# voltage_sensor_v0_7.net
KiCad netlist of a schematic drawn in EAGLE
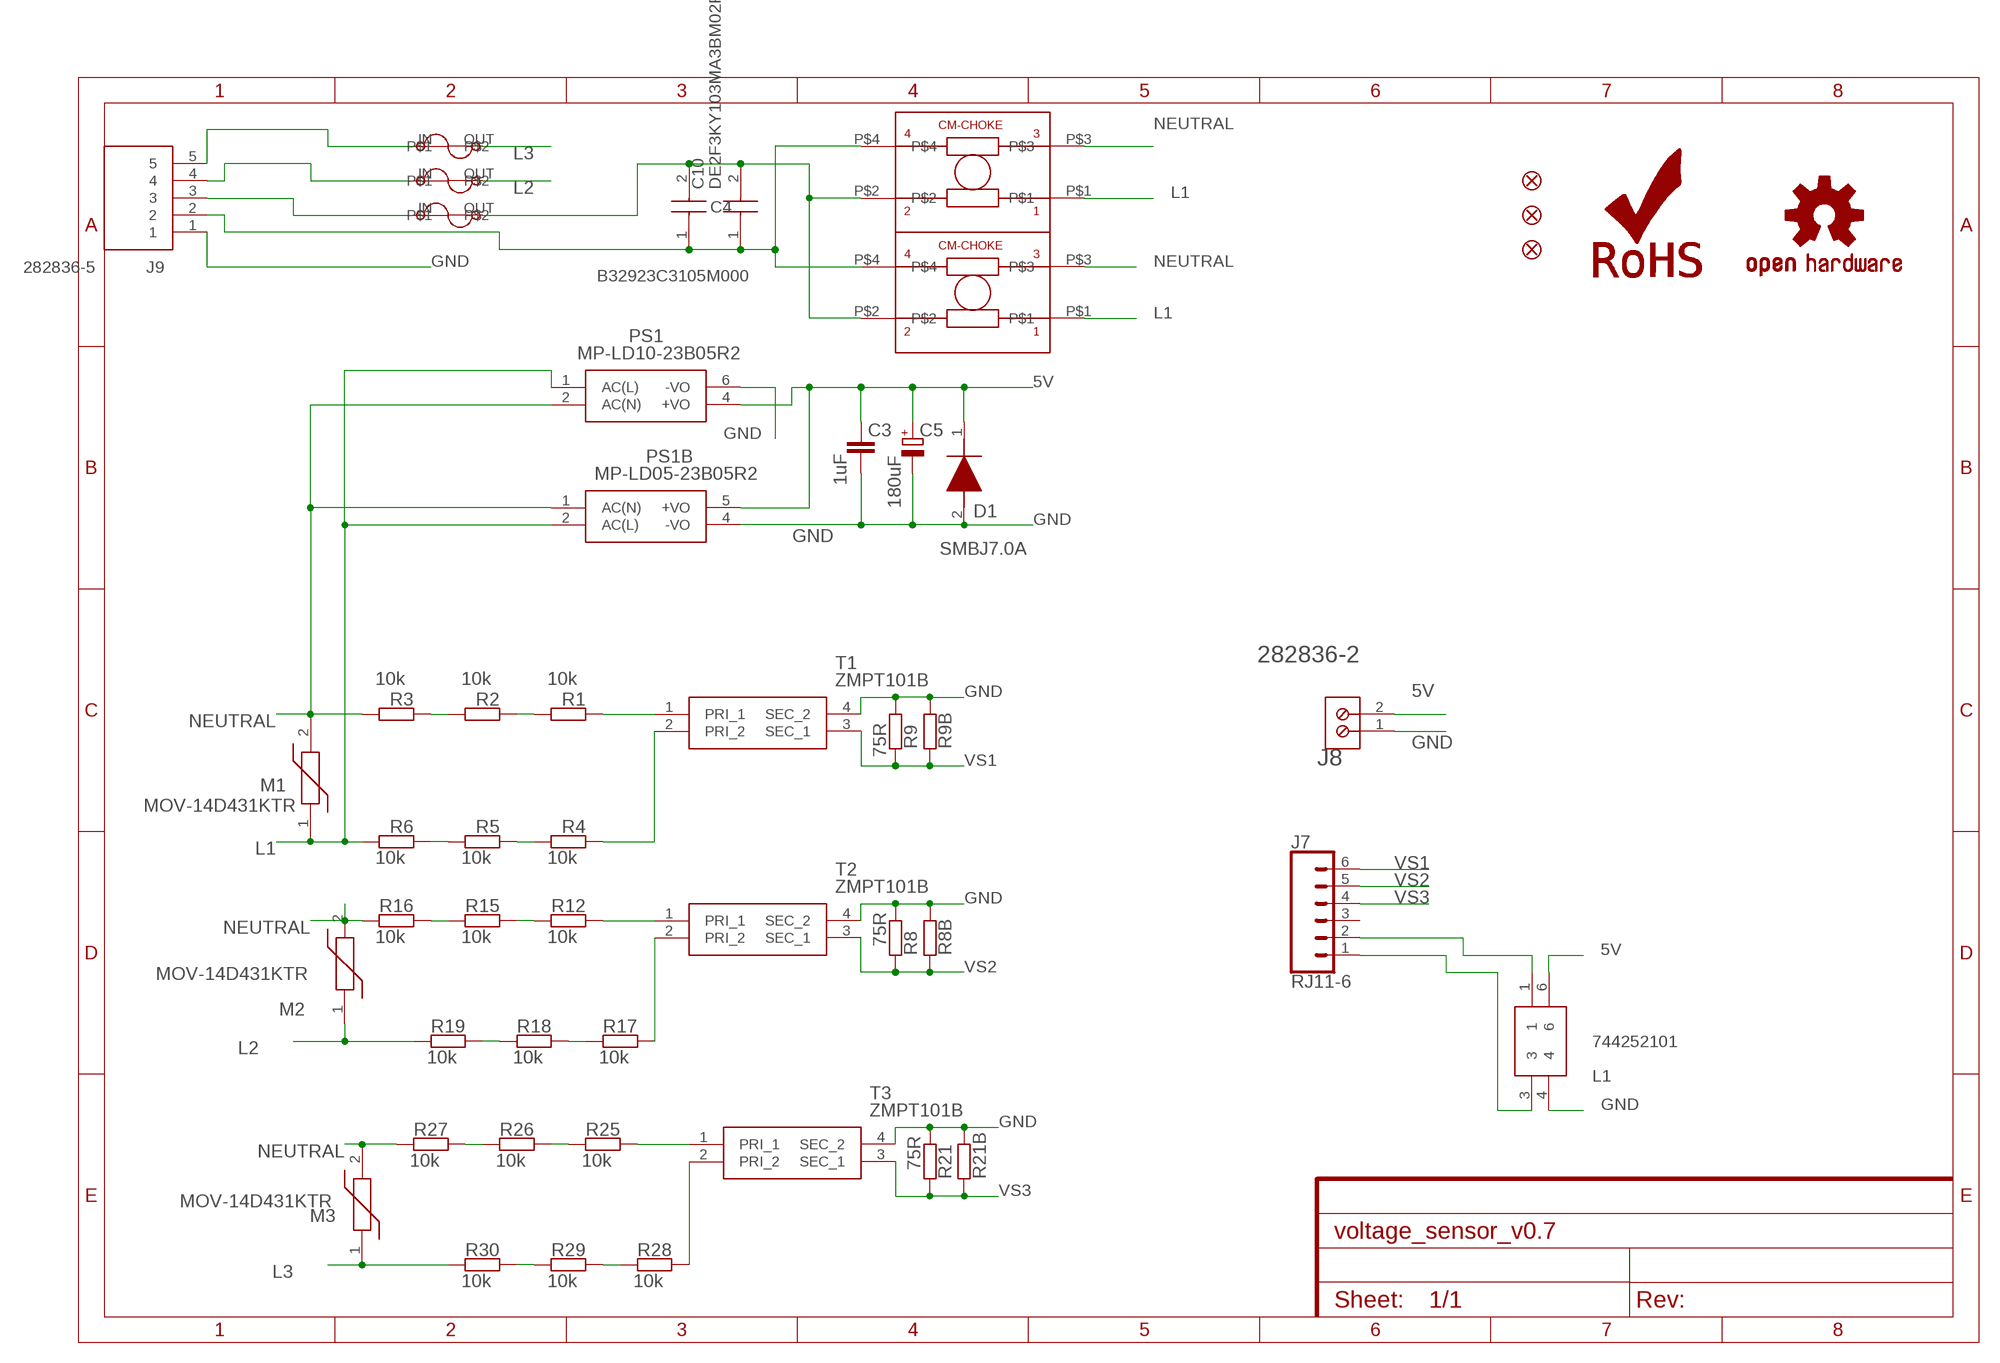
[diagram p0: schematic, sheet 1]

(export (version "E")
  (design (tool "Eeschema 10.0.6"))
  (components
    (comp (ref "C3")
      (value "1uF")
      (footprint "eagle-import:C0603")
      (libsource (lib "eagle-import") (part "C-EUC0603"))
    )
    (comp (ref "C4")
      (value "B32923C3105M000")
      (footprint "eagle-import:B32923C_(26.5_X_12)")
      (libsource (lib "eagle-import") (part "B32923C3105M000"))
    )
    (comp (ref "C5")
      (value "180uF")
      (footprint "eagle-import:PANASONIC_C")
      (libsource (lib "eagle-import") (part "CPOL-EUC"))
    )
    (comp (ref "C10")
      (value "DE2F3KY103MA3BM02F")
      (footprint "eagle-import:DE2F3KY103MA3BM02F")
      (fields (field (name "MOUSER_PART_NUMBER") "81-DE2F3KY103MA3BM2F"))
      (libsource (lib "eagle-import") (part "DE2F3KY103MA3BM02F"))
    )
    (comp (ref "D1")
      (value "SMBJ7.0A")
      (footprint "eagle-import:DIOM5336X244N")
      (libsource (lib "eagle-import") (part "SMBJ7.0A"))
    )
    (comp (ref "F1")
      (value "2A/250V")
      (footprint "eagle-import:BELFUSE1A")
      (libsource (lib "eagle-import") (part "BEL1AFUSE"))
    )
    (comp (ref "F2")
      (value "2A/250V")
      (footprint "eagle-import:BELFUSE1A")
      (libsource (lib "eagle-import") (part "BEL1AFUSE"))
    )
    (comp (ref "F3")
      (value "2A/250V")
      (footprint "eagle-import:BELFUSE1A")
      (libsource (lib "eagle-import") (part "BEL1AFUSE"))
    )
    (comp (ref "FD1")
      (value "FIDUCIAL1X2")
      (footprint "eagle-import:FIDUCIAL-1X2")
      (libsource (lib "eagle-import") (part "FIDUCIAL1X2"))
    )
    (comp (ref "FD2")
      (value "FIDUCIAL1X2")
      (footprint "eagle-import:FIDUCIAL-1X2")
      (libsource (lib "eagle-import") (part "FIDUCIAL1X2"))
    )
    (comp (ref "FD3")
      (value "FIDUCIAL1X2")
      (footprint "eagle-import:FIDUCIAL-1X2")
      (libsource (lib "eagle-import") (part "FIDUCIAL1X2"))
    )
    (comp (ref "J7")
      (value "RJ11-6")
      (footprint "eagle-import:RJ11-6")
      (libsource (lib "eagle-import") (part "RJ11-6"))
    )
    (comp (ref "J8")
      (value "TE_CONNECTIVITY_282836-2TE_CONNECTIVITY_282836-2_0_0")
      (footprint "eagle-import:TE_CONNECTIVITY_282836-2_0")
      (fields
        (field (name "MF") "TE Connectivity")
        (field (name "MPN") "282836-2")
        (field (name "VOLTAGE") "300V")
      )
      (libsource (lib "eagle-import") (part "TE_CONNECTIVITY_282836-2TE_CONNECTIVITY_282836-2_0_0"))
    )
    (comp (ref "J9")
      (value "282836-5")
      (footprint "eagle-import:2828365")
      (fields (field (name "MOUSER_PART_NUMBER") "571-2828365"))
      (libsource (lib "eagle-import") (part "282836-5"))
    )
    (comp (ref "L1")
      (value "744252101")
      (footprint "eagle-import:744252101")
      (fields (field (name "MOUSER_PART_NUMBER") "710-744252101"))
      (libsource (lib "eagle-import") (part "744252101"))
    )
    (comp (ref "LOGO1")
      (value "ROHS_LOGO")
      (footprint "eagle-import:ROHS_LOGO_0.18_IN")
      (libsource (lib "eagle-import") (part "ROHS_LOGO"))
    )
    (comp (ref "LOGO2")
      (value "OSHW-LOGOS-COPPER")
      (footprint "eagle-import:OSHW-LOGO-S_COPPER")
      (libsource (lib "eagle-import") (part "OSHW-LOGOS-COPPER"))
    )
    (comp (ref "M1")
      (value "MOV-14D431KTR")
      (footprint "eagle-import:MOV14D431KTR")
      (fields (field (name "MOUSER_PART_NUMBER") "652-MOV-14D431KTR"))
      (libsource (lib "eagle-import") (part "MOV-14D431KTR"))
    )
    (comp (ref "M2")
      (value "MOV-14D431KTR")
      (footprint "eagle-import:MOV14D431KTR")
      (fields (field (name "MOUSER_PART_NUMBER") "652-MOV-14D431KTR"))
      (libsource (lib "eagle-import") (part "MOV-14D431KTR"))
    )
    (comp (ref "M3")
      (value "MOV-14D431KTR")
      (footprint "eagle-import:MOV14D431KTR")
      (fields (field (name "MOUSER_PART_NUMBER") "652-MOV-14D431KTR"))
      (libsource (lib "eagle-import") (part "MOV-14D431KTR"))
    )
    (comp (ref "PS1")
      (value "MP-LD10-23B05R2")
      (footprint "eagle-import:MPLD1023B12R2")
      (libsource (lib "eagle-import") (part "MP-LD10-23B12R2"))
    )
    (comp (ref "PS1B")
      (value "MP-LD05-23B05R2")
      (footprint "eagle-import:MPLD0523B03R2")
      (fields (field (name "MANUFACTURER_PART_NUMBER") "MP-LD05-23B03R2"))
      (libsource (lib "eagle-import") (part "MP-LD05-23B03R2"))
    )
    (comp (ref "R1")
      (value "10k")
      (footprint "eagle-import:R0603")
      (libsource (lib "eagle-import") (part "R-EU_R0603"))
    )
    (comp (ref "R2")
      (value "10k")
      (footprint "eagle-import:R0603")
      (libsource (lib "eagle-import") (part "R-EU_R0603"))
    )
    (comp (ref "R3")
      (value "10k")
      (footprint "eagle-import:R0603")
      (libsource (lib "eagle-import") (part "R-EU_R0603"))
    )
    (comp (ref "R4")
      (value "10k")
      (footprint "eagle-import:R0603")
      (libsource (lib "eagle-import") (part "R-EU_R0603"))
    )
    (comp (ref "R5")
      (value "10k")
      (footprint "eagle-import:R0603")
      (libsource (lib "eagle-import") (part "R-EU_R0603"))
    )
    (comp (ref "R6")
      (value "10k")
      (footprint "eagle-import:R0603")
      (libsource (lib "eagle-import") (part "R-EU_R0603"))
    )
    (comp (ref "R8")
      (value "75R")
      (footprint "eagle-import:R0603")
      (libsource (lib "eagle-import") (part "R-EU_R0603"))
    )
    (comp (ref "R8B")
      (value "R-EU_0204/7")
      (footprint "eagle-import:0204_7")
      (libsource (lib "eagle-import") (part "R-EU_0204/7"))
    )
    (comp (ref "R9")
      (value "75R")
      (footprint "eagle-import:R0603")
      (libsource (lib "eagle-import") (part "R-EU_R0603"))
    )
    (comp (ref "R9B")
      (value "R-EU_0204/7")
      (footprint "eagle-import:0204_7")
      (libsource (lib "eagle-import") (part "R-EU_0204/7"))
    )
    (comp (ref "R12")
      (value "10k")
      (footprint "eagle-import:R0603")
      (libsource (lib "eagle-import") (part "R-EU_R0603"))
    )
    (comp (ref "R15")
      (value "10k")
      (footprint "eagle-import:R0603")
      (libsource (lib "eagle-import") (part "R-EU_R0603"))
    )
    (comp (ref "R16")
      (value "10k")
      (footprint "eagle-import:R0603")
      (libsource (lib "eagle-import") (part "R-EU_R0603"))
    )
    (comp (ref "R17")
      (value "10k")
      (footprint "eagle-import:R0603")
      (libsource (lib "eagle-import") (part "R-EU_R0603"))
    )
    (comp (ref "R18")
      (value "10k")
      (footprint "eagle-import:R0603")
      (libsource (lib "eagle-import") (part "R-EU_R0603"))
    )
    (comp (ref "R19")
      (value "10k")
      (footprint "eagle-import:R0603")
      (libsource (lib "eagle-import") (part "R-EU_R0603"))
    )
    (comp (ref "R21")
      (value "75R")
      (footprint "eagle-import:R0603")
      (libsource (lib "eagle-import") (part "R-EU_R0603"))
    )
    (comp (ref "R21B")
      (value "R-EU_0204/7")
      (footprint "eagle-import:0204_7")
      (libsource (lib "eagle-import") (part "R-EU_0204/7"))
    )
    (comp (ref "R25")
      (value "10k")
      (footprint "eagle-import:R0603")
      (libsource (lib "eagle-import") (part "R-EU_R0603"))
    )
    (comp (ref "R26")
      (value "10k")
      (footprint "eagle-import:R0603")
      (libsource (lib "eagle-import") (part "R-EU_R0603"))
    )
    (comp (ref "R27")
      (value "10k")
      (footprint "eagle-import:R0603")
      (libsource (lib "eagle-import") (part "R-EU_R0603"))
    )
    (comp (ref "R28")
      (value "10k")
      (footprint "eagle-import:R0603")
      (libsource (lib "eagle-import") (part "R-EU_R0603"))
    )
    (comp (ref "R29")
      (value "10k")
      (footprint "eagle-import:R0603")
      (libsource (lib "eagle-import") (part "R-EU_R0603"))
    )
    (comp (ref "R30")
      (value "10k")
      (footprint "eagle-import:R0603")
      (libsource (lib "eagle-import") (part "R-EU_R0603"))
    )
    (comp (ref "T1")
      (value "ZMPT101B")
      (footprint "eagle-import:ZMPT101B")
      (libsource (lib "eagle-import") (part "ZMPT101B"))
    )
    (comp (ref "T2")
      (value "ZMPT101B")
      (footprint "eagle-import:ZMPT101B")
      (libsource (lib "eagle-import") (part "ZMPT101B"))
    )
    (comp (ref "T3")
      (value "ZMPT101B")
      (footprint "eagle-import:ZMPT101B")
      (libsource (lib "eagle-import") (part "ZMPT101B"))
    )
    (comp (ref "U$1")
      (value "47mH")
      (footprint "eagle-import:RN114-0.3-02-47M")
      (libsource (lib "eagle-import") (part "RN114-0.3-02-47M"))
    )
    (comp (ref "U$1B")
      (value "RN214-0.3-02-47M")
      (footprint "eagle-import:RN214-0.3-02-47M")
      (libsource (lib "eagle-import") (part "RN214-0.3-02-47M"))
    )
  )
  (nets
    (net (code "1") (name "/5V") (class "Default")
      (node (ref "C3") (pin "1") (pinfunction "1_1") (pintype "passive"))
      (node (ref "C5") (pin "+") (pinfunction "+_+") (pintype "passive"))
      (node (ref "D1") (pin "1") (pinfunction "K_1") (pintype "bidirectional"))
      (node (ref "J8") (pin "2") (pinfunction "2_2") (pintype "passive"))
      (node (ref "L1") (pin "6") (pinfunction "6_6") (pintype "bidirectional"))
      (node (ref "PS1") (pin "4") (pinfunction "+VO_4") (pintype "bidirectional"))
      (node (ref "PS1B") (pin "5") (pinfunction "+VO_5") (pintype "bidirectional"))
    )
    (net (code "2") (name "/GND") (class "Default")
      (node (ref "C3") (pin "2") (pinfunction "2_2") (pintype "passive"))
      (node (ref "C5") (pin "-") (pinfunction "-_-") (pintype "passive"))
      (node (ref "D1") (pin "2") (pinfunction "A_2") (pintype "bidirectional"))
      (node (ref "J8") (pin "1") (pinfunction "1_1") (pintype "passive"))
      (node (ref "J9") (pin "1") (pinfunction "1_1") (pintype "bidirectional"))
      (node (ref "L1") (pin "4") (pinfunction "4_4") (pintype "bidirectional"))
      (node (ref "PS1") (pin "6") (pinfunction "-VO_6") (pintype "bidirectional"))
      (node (ref "PS1B") (pin "4") (pinfunction "-VO_4") (pintype "bidirectional"))
      (node (ref "R21") (pin "2") (pinfunction "2_2") (pintype "passive"))
      (node (ref "R21B") (pin "2") (pinfunction "2_2") (pintype "passive"))
      (node (ref "R8") (pin "2") (pinfunction "2_2") (pintype "passive"))
      (node (ref "R8B") (pin "2") (pinfunction "2_2") (pintype "passive"))
      (node (ref "R9") (pin "2") (pinfunction "2_2") (pintype "passive"))
      (node (ref "R9B") (pin "2") (pinfunction "2_2") (pintype "passive"))
      (node (ref "T1") (pin "4") (pinfunction "SEC_2_4") (pintype "bidirectional"))
      (node (ref "T2") (pin "4") (pinfunction "SEC_2_4") (pintype "bidirectional"))
      (node (ref "T3") (pin "4") (pinfunction "SEC_2_4") (pintype "bidirectional"))
    )
    (net (code "3") (name "/L1") (class "Default")
      (node (ref "M1") (pin "1") (pinfunction "1_1") (pintype "bidirectional"))
      (node (ref "PS1") (pin "1") (pinfunction "AC(L)_1") (pintype "bidirectional"))
      (node (ref "PS1B") (pin "2") (pinfunction "AC(L)_2") (pintype "bidirectional"))
      (node (ref "R6") (pin "2") (pinfunction "2_2") (pintype "passive"))
      (node (ref "U$1") (pin "P$1") (pinfunction "P$1_P$1") (pintype "bidirectional"))
      (node (ref "U$1B") (pin "P$1") (pinfunction "P$1_P$1") (pintype "bidirectional"))
    )
    (net (code "4") (name "/L2") (class "Default")
      (node (ref "F2") (pin "OUT") (pinfunction "P$1_OUT") (pintype "bidirectional"))
      (node (ref "M2") (pin "1") (pinfunction "1_1") (pintype "bidirectional"))
      (node (ref "R19") (pin "2") (pinfunction "2_2") (pintype "passive"))
    )
    (net (code "5") (name "/L3") (class "Default")
      (node (ref "F3") (pin "OUT") (pinfunction "P$1_OUT") (pintype "bidirectional"))
      (node (ref "M3") (pin "1") (pinfunction "1_1") (pintype "bidirectional"))
      (node (ref "R30") (pin "2") (pinfunction "2_2") (pintype "passive"))
    )
    (net (code "6") (name "/NEUTRAL") (class "Default")
      (node (ref "M1") (pin "2") (pinfunction "2_2") (pintype "bidirectional"))
      (node (ref "M2") (pin "2") (pinfunction "2_2") (pintype "bidirectional"))
      (node (ref "M3") (pin "2") (pinfunction "2_2") (pintype "bidirectional"))
      (node (ref "PS1") (pin "2") (pinfunction "AC(N)_2") (pintype "bidirectional"))
      (node (ref "PS1B") (pin "1") (pinfunction "AC(N)_1") (pintype "bidirectional"))
      (node (ref "R16") (pin "2") (pinfunction "2_2") (pintype "passive"))
      (node (ref "R27") (pin "2") (pinfunction "2_2") (pintype "passive"))
      (node (ref "R3") (pin "2") (pinfunction "2_2") (pintype "passive"))
      (node (ref "U$1") (pin "P$3") (pinfunction "P$3_P$3") (pintype "bidirectional"))
      (node (ref "U$1B") (pin "P$3") (pinfunction "P$3_P$3") (pintype "bidirectional"))
    )
    (net (code "7") (name "/VS1") (class "Default")
      (node (ref "J7") (pin "6") (pinfunction "6_6") (pintype "passive"))
      (node (ref "R9") (pin "1") (pinfunction "1_1") (pintype "passive"))
      (node (ref "R9B") (pin "1") (pinfunction "1_1") (pintype "passive"))
      (node (ref "T1") (pin "3") (pinfunction "SEC_1_3") (pintype "bidirectional"))
    )
    (net (code "8") (name "/VS2") (class "Default")
      (node (ref "J7") (pin "5") (pinfunction "5_5") (pintype "passive"))
      (node (ref "R8") (pin "1") (pinfunction "1_1") (pintype "passive"))
      (node (ref "R8B") (pin "1") (pinfunction "1_1") (pintype "passive"))
      (node (ref "T2") (pin "3") (pinfunction "SEC_1_3") (pintype "bidirectional"))
    )
    (net (code "9") (name "/VS3") (class "Default")
      (node (ref "J7") (pin "4") (pinfunction "4_4") (pintype "passive"))
      (node (ref "R21") (pin "1") (pinfunction "1_1") (pintype "passive"))
      (node (ref "R21B") (pin "1") (pinfunction "1_1") (pintype "passive"))
      (node (ref "T3") (pin "3") (pinfunction "SEC_1_3") (pintype "bidirectional"))
    )
    (net (code "10") (name "Net-(C10-Pad1)") (class "Default")
      (node (ref "C10") (pin "1") (pinfunction "1_1") (pintype "bidirectional"))
      (node (ref "C4") (pin "1") (pinfunction "1_1") (pintype "bidirectional"))
      (node (ref "J9") (pin "2") (pinfunction "2_2") (pintype "bidirectional"))
      (node (ref "U$1") (pin "P$4") (pinfunction "P$4_P$4") (pintype "bidirectional"))
      (node (ref "U$1B") (pin "P$4") (pinfunction "P$4_P$4") (pintype "bidirectional"))
    )
    (net (code "11") (name "Net-(F1-P$1)") (class "Default")
      (node (ref "C10") (pin "2") (pinfunction "2_2") (pintype "bidirectional"))
      (node (ref "C4") (pin "2") (pinfunction "2_2") (pintype "bidirectional"))
      (node (ref "F1") (pin "OUT") (pinfunction "P$1_OUT") (pintype "bidirectional"))
      (node (ref "U$1") (pin "P$2") (pinfunction "P$2_P$2") (pintype "bidirectional"))
      (node (ref "U$1B") (pin "P$2") (pinfunction "P$2_P$2") (pintype "bidirectional"))
    )
    (net (code "12") (name "Net-(F1-P$2)") (class "Default")
      (node (ref "F1") (pin "IN") (pinfunction "P$2_IN") (pintype "bidirectional"))
      (node (ref "J9") (pin "3") (pinfunction "3_3") (pintype "bidirectional"))
    )
    (net (code "13") (name "Net-(F2-P$2)") (class "Default")
      (node (ref "F2") (pin "IN") (pinfunction "P$2_IN") (pintype "bidirectional"))
      (node (ref "J9") (pin "4") (pinfunction "4_4") (pintype "bidirectional"))
    )
    (net (code "14") (name "Net-(F3-P$2)") (class "Default")
      (node (ref "F3") (pin "IN") (pinfunction "P$2_IN") (pintype "bidirectional"))
      (node (ref "J9") (pin "5") (pinfunction "5_5") (pintype "bidirectional"))
    )
    (net (code "15") (name "Net-(J7-Pad1)") (class "Default")
      (node (ref "J7") (pin "1") (pinfunction "1_1") (pintype "passive"))
      (node (ref "L1") (pin "3") (pinfunction "3_3") (pintype "bidirectional"))
    )
    (net (code "16") (name "Net-(J7-Pad2)") (class "Default")
      (node (ref "J7") (pin "2") (pinfunction "2_2") (pintype "passive"))
      (node (ref "L1") (pin "1") (pinfunction "1_1") (pintype "bidirectional"))
    )
    (net (code "17") (name "Net-(R1-Pad2)") (class "Default")
      (node (ref "R1") (pin "2") (pinfunction "2_2") (pintype "passive"))
      (node (ref "R2") (pin "1") (pinfunction "1_1") (pintype "passive"))
    )
    (net (code "18") (name "Net-(R2-Pad2)") (class "Default")
      (node (ref "R2") (pin "2") (pinfunction "2_2") (pintype "passive"))
      (node (ref "R3") (pin "1") (pinfunction "1_1") (pintype "passive"))
    )
    (net (code "19") (name "Net-(R4-Pad2)") (class "Default")
      (node (ref "R4") (pin "2") (pinfunction "2_2") (pintype "passive"))
      (node (ref "R5") (pin "1") (pinfunction "1_1") (pintype "passive"))
    )
    (net (code "20") (name "Net-(R5-Pad2)") (class "Default")
      (node (ref "R5") (pin "2") (pinfunction "2_2") (pintype "passive"))
      (node (ref "R6") (pin "1") (pinfunction "1_1") (pintype "passive"))
    )
    (net (code "21") (name "Net-(R12-Pad2)") (class "Default")
      (node (ref "R12") (pin "2") (pinfunction "2_2") (pintype "passive"))
      (node (ref "R15") (pin "1") (pinfunction "1_1") (pintype "passive"))
    )
    (net (code "22") (name "Net-(R15-Pad2)") (class "Default")
      (node (ref "R15") (pin "2") (pinfunction "2_2") (pintype "passive"))
      (node (ref "R16") (pin "1") (pinfunction "1_1") (pintype "passive"))
    )
    (net (code "23") (name "Net-(R17-Pad2)") (class "Default")
      (node (ref "R17") (pin "2") (pinfunction "2_2") (pintype "passive"))
      (node (ref "R18") (pin "1") (pinfunction "1_1") (pintype "passive"))
    )
    (net (code "24") (name "Net-(R18-Pad2)") (class "Default")
      (node (ref "R18") (pin "2") (pinfunction "2_2") (pintype "passive"))
      (node (ref "R19") (pin "1") (pinfunction "1_1") (pintype "passive"))
    )
    (net (code "25") (name "Net-(R25-Pad2)") (class "Default")
      (node (ref "R25") (pin "2") (pinfunction "2_2") (pintype "passive"))
      (node (ref "R26") (pin "1") (pinfunction "1_1") (pintype "passive"))
    )
    (net (code "26") (name "Net-(R26-Pad2)") (class "Default")
      (node (ref "R26") (pin "2") (pinfunction "2_2") (pintype "passive"))
      (node (ref "R27") (pin "1") (pinfunction "1_1") (pintype "passive"))
    )
    (net (code "27") (name "Net-(R28-Pad2)") (class "Default")
      (node (ref "R28") (pin "2") (pinfunction "2_2") (pintype "passive"))
      (node (ref "R29") (pin "1") (pinfunction "1_1") (pintype "passive"))
    )
    (net (code "28") (name "Net-(R29-Pad2)") (class "Default")
      (node (ref "R29") (pin "2") (pinfunction "2_2") (pintype "passive"))
      (node (ref "R30") (pin "1") (pinfunction "1_1") (pintype "passive"))
    )
    (net (code "29") (name "Net-(T1-PRI_1)") (class "Default")
      (node (ref "R1") (pin "1") (pinfunction "1_1") (pintype "passive"))
      (node (ref "T1") (pin "1") (pinfunction "PRI_1_1") (pintype "bidirectional"))
    )
    (net (code "30") (name "Net-(T1-PRI_2)") (class "Default")
      (node (ref "R4") (pin "1") (pinfunction "1_1") (pintype "passive"))
      (node (ref "T1") (pin "2") (pinfunction "PRI_2_2") (pintype "bidirectional"))
    )
    (net (code "31") (name "Net-(T2-PRI_1)") (class "Default")
      (node (ref "R12") (pin "1") (pinfunction "1_1") (pintype "passive"))
      (node (ref "T2") (pin "1") (pinfunction "PRI_1_1") (pintype "bidirectional"))
    )
    (net (code "32") (name "Net-(T2-PRI_2)") (class "Default")
      (node (ref "R17") (pin "1") (pinfunction "1_1") (pintype "passive"))
      (node (ref "T2") (pin "2") (pinfunction "PRI_2_2") (pintype "bidirectional"))
    )
    (net (code "33") (name "Net-(T3-PRI_1)") (class "Default")
      (node (ref "R25") (pin "1") (pinfunction "1_1") (pintype "passive"))
      (node (ref "T3") (pin "1") (pinfunction "PRI_1_1") (pintype "bidirectional"))
    )
    (net (code "34") (name "Net-(T3-PRI_2)") (class "Default")
      (node (ref "R28") (pin "1") (pinfunction "1_1") (pintype "passive"))
      (node (ref "T3") (pin "2") (pinfunction "PRI_2_2") (pintype "bidirectional"))
    )
    (net (code "35") (name "unconnected-(J7-Pad3)") (class "Default")
      (node (ref "J7") (pin "3") (pinfunction "3_3") (pintype "passive"))
    )
  )
)
